# LMG1025_Flasher_Shield.net
KiCad netlist of a schematic drawn in EAGLE
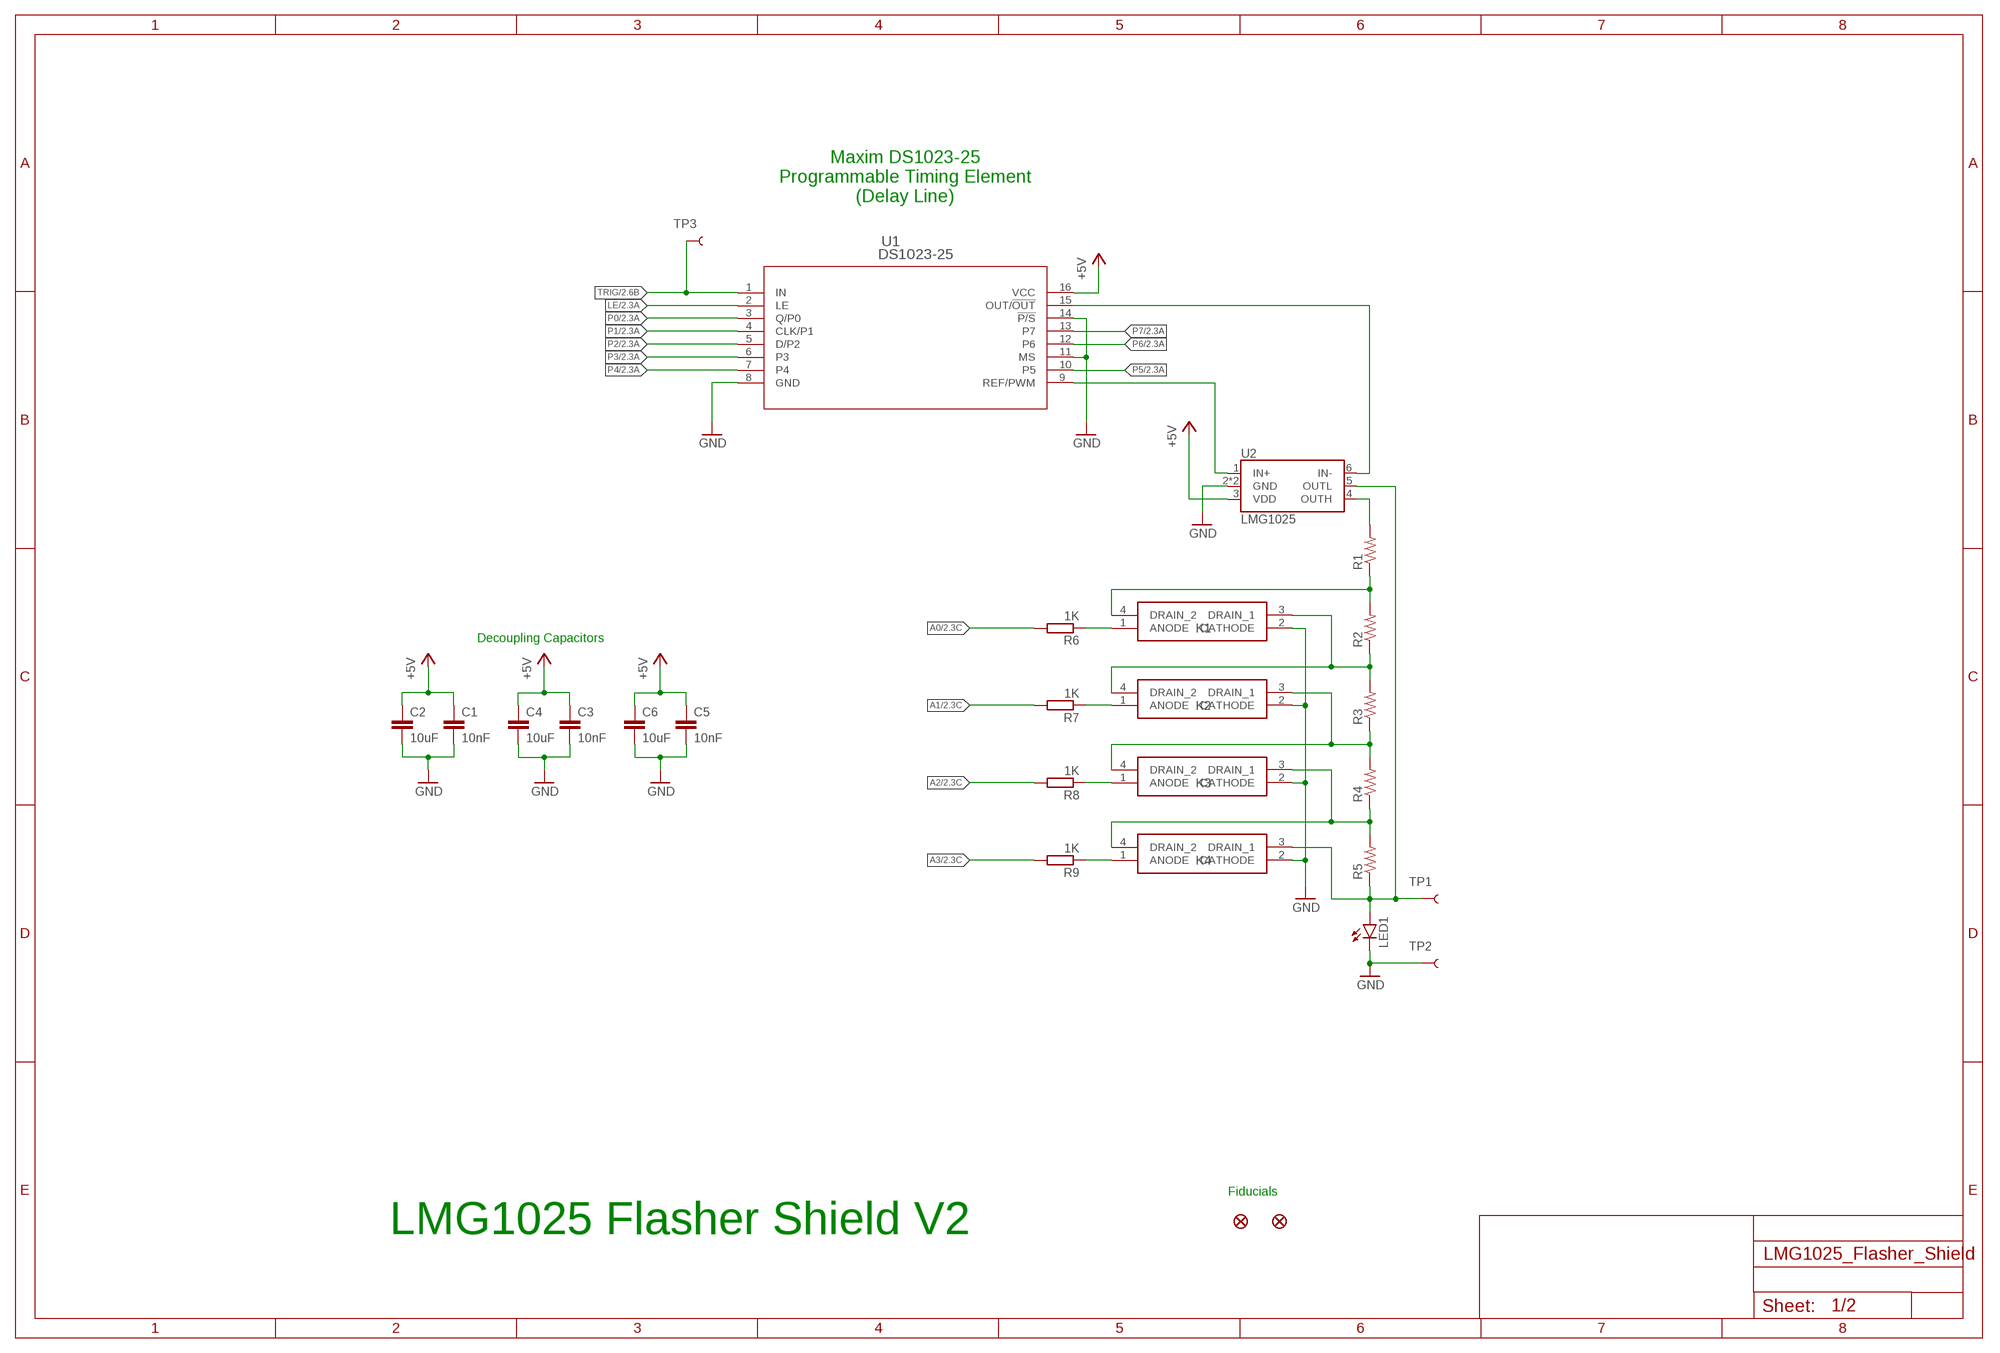
[diagram p0: schematic, sheet 1]
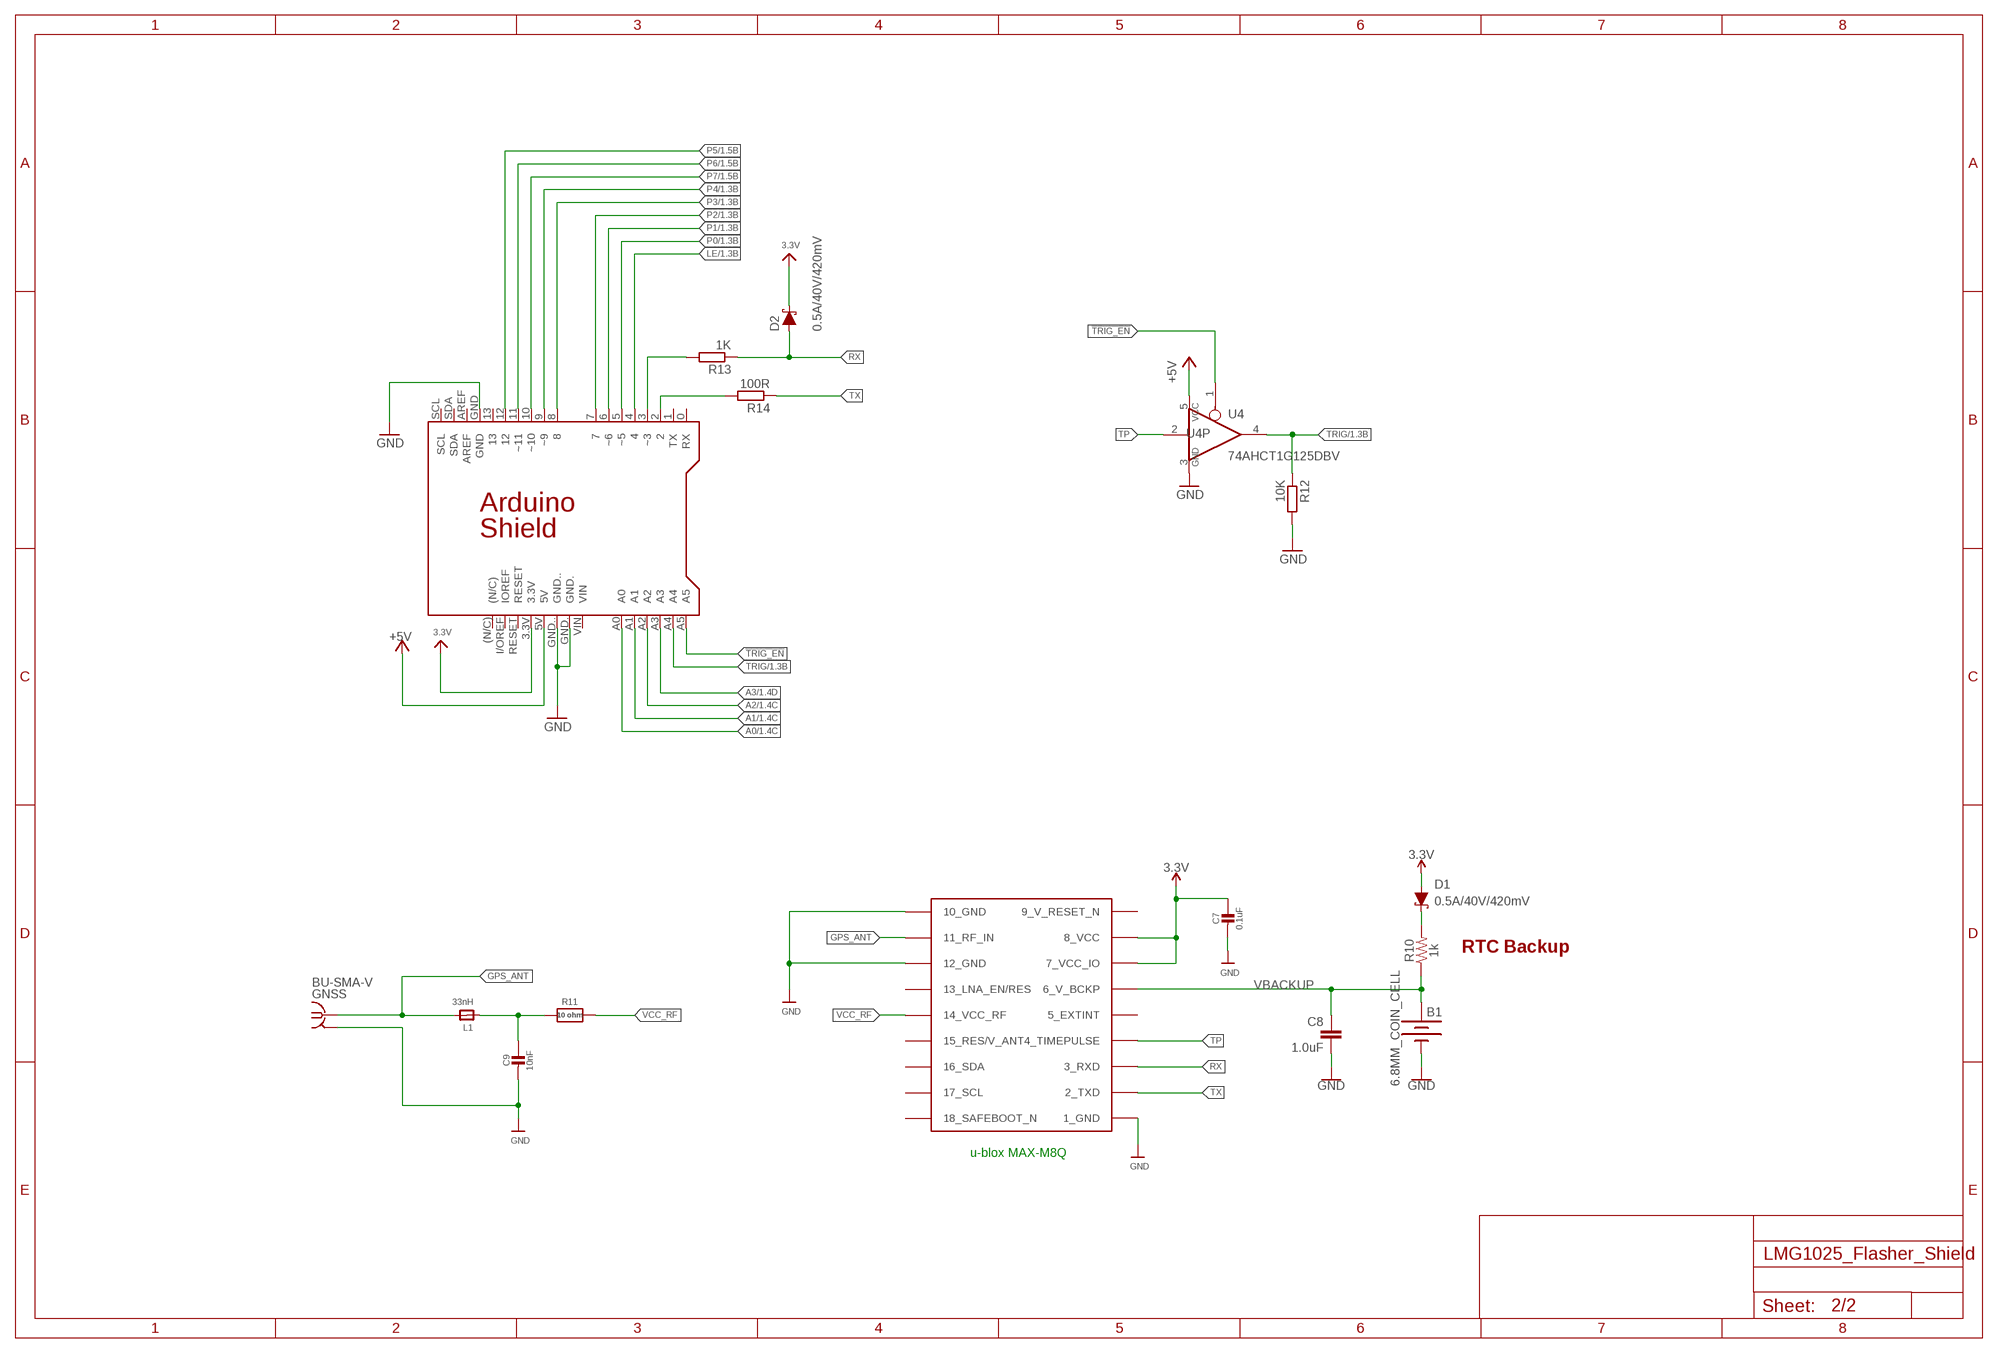
[diagram p1: schematic, sheet 2]

(export (version "E")
  (design (tool "Eeschema 10.0.6"))
  (components
    (comp (ref "B1")
      (value "6.8MM_COIN_CELL")
      (footprint "eagle-import:BATTCON-6.8MM")
      (libsource (lib "eagle-import") (part "BATTERY-6.8MM_SMD"))
    )
    (comp (ref "C7")
      (value "0.1uF")
      (footprint "eagle-import:0805-NO")
      (libsource (lib "eagle-import") (part "CAP_CERAMIC0805-NOOUTLINE"))
    )
    (comp (ref "C8")
      (value "1.0uF")
      (footprint "eagle-import:0603")
      (libsource (lib "eagle-import") (part "1.0UF-0603-16V-10%"))
    )
    (comp (ref "C9")
      (value "10nF")
      (footprint "eagle-import:0805-NO")
      (libsource (lib "eagle-import") (part "CAP_CERAMIC0805-NOOUTLINE"))
    )
    (comp (ref "D1")
      (value "0.5A/40V/420mV")
      (footprint "eagle-import:SOD-323")
      (libsource (lib "eagle-import") (part "DIODE-SCHOTTKY-PMEG4005EJ"))
    )
    (comp (ref "D2")
      (value "0.5A/40V/420mV")
      (footprint "eagle-import:SOD-323")
      (libsource (lib "eagle-import") (part "DIODE-SCHOTTKY-PMEG4005EJ"))
    )
    (comp (ref "GNSS")
      (value "BU-SMA-V")
      (footprint "eagle-import:BU-SMA-V")
      (libsource (lib "eagle-import") (part "BU-SMA-V"))
    )
    (comp (ref "L1")
      (value "33nH")
      (footprint "eagle-import:0805-NO")
      (libsource (lib "eagle-import") (part "FERRITE-0805NO"))
    )
    (comp (ref "PCB1")
      (value "CHEC_LED_DRIVER_SHIELD")
      (footprint "eagle-import:CHEC_LED_DRIVER_SHIELD")
      (libsource (lib "eagle-import") (part "CHEC_LED_DRIVER_SHIELD"))
    )
    (comp (ref "R10")
      (value "1k")
      (footprint "eagle-import:0603@1")
      (libsource (lib "eagle-import") (part "1KOHM-0603-1/10W-1%"))
    )
    (comp (ref "R11")
      (value "10 ohm")
      (footprint "eagle-import:0805-NO")
      (libsource (lib "eagle-import") (part "RESISTOR0805_NOOUTLINE"))
    )
    (comp (ref "R12")
      (value "10K")
      (footprint "eagle-import:R0603")
      (libsource (lib "eagle-import") (part "R-EU_R0603"))
    )
    (comp (ref "R13")
      (value "1K")
      (footprint "eagle-import:R0603")
      (libsource (lib "eagle-import") (part "R-EU_R0603"))
    )
    (comp (ref "R14")
      (value "100R")
      (footprint "eagle-import:R0603")
      (libsource (lib "eagle-import") (part "R-EU_R0603"))
    )
    (comp (ref "U3")
      (value "MAX-M8")
      (footprint "eagle-import:MAX-M8")
      (libsource (lib "eagle-import") (part "MAX-M8"))
    )
    (comp (ref "U4")
      (value "74AHCT1G125DBV")
      (footprint "eagle-import:SOT23-5")
      (libsource (lib "eagle-import") (part "741G125DBVAHCT"))
    )
    (comp (ref "C1")
      (value "10nF")
      (footprint "eagle-import:C0805")
      (libsource (lib "eagle-import") (part "C-EUC0805"))
    )
    (comp (ref "C2")
      (value "10uF")
      (footprint "eagle-import:C0805")
      (libsource (lib "eagle-import") (part "C-EUC0805"))
    )
    (comp (ref "C3")
      (value "10nF")
      (footprint "eagle-import:C0805")
      (libsource (lib "eagle-import") (part "C-EUC0805"))
    )
    (comp (ref "C4")
      (value "10uF")
      (footprint "eagle-import:C0805")
      (libsource (lib "eagle-import") (part "C-EUC0805"))
    )
    (comp (ref "C5")
      (value "10nF")
      (footprint "eagle-import:C0805")
      (libsource (lib "eagle-import") (part "C-EUC0805"))
    )
    (comp (ref "C6")
      (value "10uF")
      (footprint "eagle-import:C0805")
      (libsource (lib "eagle-import") (part "C-EUC0805"))
    )
    (comp (ref "FD1")
      (value "FIDUCIAL1X2")
      (footprint "eagle-import:FIDUCIAL-1X2")
      (libsource (lib "eagle-import") (part "FIDUCIAL1X2"))
    )
    (comp (ref "FD2")
      (value "FIDUCIAL1X2")
      (footprint "eagle-import:FIDUCIAL-1X2")
      (libsource (lib "eagle-import") (part "FIDUCIAL1X2"))
    )
    (comp (ref "K1")
      (value "TLP3475R(TP,F")
      (footprint "eagle-import:TLP3475RTPF")
      (fields (field (name "MOUSER_PART_NUMBER") "757-TLP3475RTPF"))
      (libsource (lib "eagle-import") (part "TLP3475R(TP,F"))
    )
    (comp (ref "K2")
      (value "TLP3475R(TP,F")
      (footprint "eagle-import:TLP3475RTPF")
      (fields (field (name "MOUSER_PART_NUMBER") "757-TLP3475RTPF"))
      (libsource (lib "eagle-import") (part "TLP3475R(TP,F"))
    )
    (comp (ref "K3")
      (value "TLP3475R(TP,F")
      (footprint "eagle-import:TLP3475RTPF")
      (fields (field (name "MOUSER_PART_NUMBER") "757-TLP3475RTPF"))
      (libsource (lib "eagle-import") (part "TLP3475R(TP,F"))
    )
    (comp (ref "K4")
      (value "TLP3475R(TP,F")
      (footprint "eagle-import:TLP3475RTPF")
      (fields (field (name "MOUSER_PART_NUMBER") "757-TLP3475RTPF"))
      (libsource (lib "eagle-import") (part "TLP3475R(TP,F"))
    )
    (comp (ref "LED1")
      (value "LED3MM")
      (footprint "eagle-import:LED3MM")
      (libsource (lib "eagle-import") (part "LED3MM"))
    )
    (comp (ref "R1")
      (value "RESISTOR0805-RES")
      (footprint "eagle-import:0805")
      (libsource (lib "eagle-import") (part "RESISTOR0805-RES"))
    )
    (comp (ref "R2")
      (value "RESISTOR0805-RES")
      (footprint "eagle-import:0805")
      (libsource (lib "eagle-import") (part "RESISTOR0805-RES"))
    )
    (comp (ref "R3")
      (value "RESISTOR0805-RES")
      (footprint "eagle-import:0805")
      (libsource (lib "eagle-import") (part "RESISTOR0805-RES"))
    )
    (comp (ref "R4")
      (value "RESISTOR0805-RES")
      (footprint "eagle-import:0805")
      (libsource (lib "eagle-import") (part "RESISTOR0805-RES"))
    )
    (comp (ref "R5")
      (value "RESISTOR0805-RES")
      (footprint "eagle-import:0805")
      (libsource (lib "eagle-import") (part "RESISTOR0805-RES"))
    )
    (comp (ref "R6")
      (value "1K")
      (footprint "eagle-import:R0603")
      (libsource (lib "eagle-import") (part "R-EU_R0603"))
    )
    (comp (ref "R7")
      (value "1K")
      (footprint "eagle-import:R0603")
      (libsource (lib "eagle-import") (part "R-EU_R0603"))
    )
    (comp (ref "R8")
      (value "1K")
      (footprint "eagle-import:R0603")
      (libsource (lib "eagle-import") (part "R-EU_R0603"))
    )
    (comp (ref "R9")
      (value "1K")
      (footprint "eagle-import:R0603")
      (libsource (lib "eagle-import") (part "R-EU_R0603"))
    )
    (comp (ref "TP1")
      (value "TEST-POINTPOGO_PTH")
      (footprint "eagle-import:1X01_NO_SILK")
      (libsource (lib "eagle-import") (part "TEST-POINTPOGO_PTH"))
    )
    (comp (ref "TP2")
      (value "TEST-POINTPOGO_PTH")
      (footprint "eagle-import:1X01_NO_SILK")
      (libsource (lib "eagle-import") (part "TEST-POINTPOGO_PTH"))
    )
    (comp (ref "TP3")
      (value "TEST-POINTPOGO_PTH")
      (footprint "eagle-import:1X01_NO_SILK")
      (libsource (lib "eagle-import") (part "TEST-POINTPOGO_PTH"))
    )
    (comp (ref "U1")
      (value "DS1023-25")
      (footprint "eagle-import:21-0042B_16")
      (fields (field (name "MANUFACTURER_PART_NUMBER") "DS102325"))
      (libsource (lib "eagle-import") (part "DS1023-25"))
    )
    (comp (ref "U2")
      (value "LMG1025")
      (footprint "eagle-import:LMG1025")
      (libsource (lib "eagle-import") (part "LMG1025"))
    )
  )
  (nets
    (net (code "1") (name "+5V") (class "Default")
      (node (ref "C1") (pin "1") (pinfunction "1_1") (pintype "passive"))
      (node (ref "C2") (pin "1") (pinfunction "1_1") (pintype "passive"))
      (node (ref "C3") (pin "1") (pinfunction "1_1") (pintype "passive"))
      (node (ref "C4") (pin "1") (pinfunction "1_1") (pintype "passive"))
      (node (ref "C5") (pin "1") (pinfunction "1_1") (pintype "passive"))
      (node (ref "C6") (pin "1") (pinfunction "1_1") (pintype "passive"))
      (node (ref "PCB1") (pin "5V") (pinfunction "5V_5V") (pintype "bidirectional"))
      (node (ref "U1") (pin "16") (pinfunction "VCC_16") (pintype "power_in"))
      (node (ref "U2") (pin "3") (pinfunction "VDD_3") (pintype "power_in"))
      (node (ref "U4") (pin "5") (pinfunction "VCC_5") (pintype "power_in"))
    )
    (net (code "2") (name "3.3V") (class "Default")
      (node (ref "C7") (pin "1") (pinfunction "1_1") (pintype "passive"))
      (node (ref "D1") (pin "A") (pinfunction "A_A") (pintype "passive"))
      (node (ref "D2") (pin "C") (pinfunction "C_C") (pintype "passive"))
      (node (ref "PCB1") (pin "3.3V") (pinfunction "3.3V_3.3V") (pintype "bidirectional"))
      (node (ref "U3") (pin "7_VCC_IO") (pinfunction "7_VCC_IO_7_VCC_IO") (pintype "power_in"))
      (node (ref "U3") (pin "8_VCC") (pinfunction "8_VCC_8_VCC") (pintype "power_in"))
    )
    (net (code "3") (name "9_V_RESET_N") (class "Default")
      (node (ref "U3") (pin "9_RESET_N") (pinfunction "9_V_RESET_N_9_RESET_N") (pintype "power_in"))
    )
    (net (code "4") (name "A0") (class "Default")
      (node (ref "PCB1") (pin "A0") (pinfunction "A0_A0") (pintype "bidirectional"))
      (node (ref "R6") (pin "2") (pinfunction "2_2") (pintype "passive"))
    )
    (net (code "5") (name "A1") (class "Default")
      (node (ref "PCB1") (pin "A1") (pinfunction "A1_A1") (pintype "bidirectional"))
      (node (ref "R7") (pin "2") (pinfunction "2_2") (pintype "passive"))
    )
    (net (code "6") (name "A2") (class "Default")
      (node (ref "PCB1") (pin "A2") (pinfunction "A2_A2") (pintype "bidirectional"))
      (node (ref "R8") (pin "2") (pinfunction "2_2") (pintype "passive"))
    )
    (net (code "7") (name "A3") (class "Default")
      (node (ref "PCB1") (pin "A3") (pinfunction "A3_A3") (pintype "bidirectional"))
      (node (ref "R9") (pin "2") (pinfunction "2_2") (pintype "passive"))
    )
    (net (code "8") (name "GND") (class "Default")
      (node (ref "B1") (pin "-") (pinfunction "-_-") (pintype "power_in"))
      (node (ref "C1") (pin "2") (pinfunction "2_2") (pintype "passive"))
      (node (ref "C2") (pin "2") (pinfunction "2_2") (pintype "passive"))
      (node (ref "C3") (pin "2") (pinfunction "2_2") (pintype "passive"))
      (node (ref "C4") (pin "2") (pinfunction "2_2") (pintype "passive"))
      (node (ref "C5") (pin "2") (pinfunction "2_2") (pintype "passive"))
      (node (ref "C6") (pin "2") (pinfunction "2_2") (pintype "passive"))
      (node (ref "C7") (pin "2") (pinfunction "2_2") (pintype "passive"))
      (node (ref "C8") (pin "2") (pinfunction "2_2") (pintype "passive"))
      (node (ref "C9") (pin "2") (pinfunction "2_2") (pintype "passive"))
      (node (ref "GNSS") (pin "2") (pinfunction "2_2") (pintype "passive"))
      (node (ref "GNSS") (pin "3") (pinfunction "2_3") (pintype "passive"))
      (node (ref "GNSS") (pin "4") (pinfunction "2_4") (pintype "passive"))
      (node (ref "GNSS") (pin "5") (pinfunction "2_5") (pintype "passive"))
      (node (ref "K1") (pin "2") (pinfunction "CATHODE_2") (pintype "bidirectional"))
      (node (ref "K2") (pin "2") (pinfunction "CATHODE_2") (pintype "bidirectional"))
      (node (ref "K3") (pin "2") (pinfunction "CATHODE_2") (pintype "bidirectional"))
      (node (ref "K4") (pin "2") (pinfunction "CATHODE_2") (pintype "bidirectional"))
      (node (ref "LED1") (pin "K") (pinfunction "C_K") (pintype "passive"))
      (node (ref "PCB1") (pin "GND") (pinfunction "GND_GND") (pintype "bidirectional"))
      (node (ref "PCB1") (pin "GND.") (pinfunction "GND._GND.") (pintype "bidirectional"))
      (node (ref "PCB1") (pin "GND..") (pinfunction "GND.._GND..") (pintype "bidirectional"))
      (node (ref "R12") (pin "2") (pinfunction "2_2") (pintype "passive"))
      (node (ref "TP2") (pin "1") (pinfunction "1_1") (pintype "bidirectional"))
      (node (ref "U1") (pin "11") (pinfunction "MS_11") (pintype "passive"))
      (node (ref "U1") (pin "14") (pinfunction "~{P/S}_14") (pintype "passive"))
      (node (ref "U1") (pin "8") (pinfunction "GND_8") (pintype "power_in"))
      (node (ref "U2") (pin "2") (pinfunction "GND_2") (pintype "power_in"))
      (node (ref "U2") (pin "PAD") (pinfunction "GND_PAD") (pintype "power_in"))
      (node (ref "U3") (pin "10_GND") (pinfunction "10_GND_10_GND") (pintype "power_in"))
      (node (ref "U3") (pin "12_GND") (pinfunction "12_GND_12_GND") (pintype "power_in"))
      (node (ref "U3") (pin "1_GND") (pinfunction "1_GND_1_GND") (pintype "power_in"))
      (node (ref "U4") (pin "3") (pinfunction "GND_3") (pintype "power_in"))
    )
    (net (code "9") (name "GPS_ANT") (class "Default")
      (node (ref "GNSS") (pin "1") (pinfunction "1_1") (pintype "passive"))
      (node (ref "L1") (pin "2") (pinfunction "P$2_2") (pintype "passive"))
      (node (ref "U3") (pin "11_RF_IN") (pinfunction "11_RF_IN_11_RF_IN") (pintype "bidirectional"))
    )
    (net (code "10") (name "LE") (class "Default")
      (node (ref "PCB1") (pin "4") (pinfunction "4_4") (pintype "bidirectional"))
      (node (ref "U1") (pin "2") (pinfunction "LE_2") (pintype "passive"))
    )
    (net (code "11") (name "Net-(D1-PadC)") (class "Default")
      (node (ref "D1") (pin "C") (pinfunction "C_C") (pintype "passive"))
      (node (ref "R10") (pin "2") (pinfunction "2_2") (pintype "passive"))
    )
    (net (code "12") (name "Net-(K1-ANODE)") (class "Default")
      (node (ref "K1") (pin "1") (pinfunction "ANODE_1") (pintype "bidirectional"))
      (node (ref "R6") (pin "1") (pinfunction "1_1") (pintype "passive"))
    )
    (net (code "13") (name "Net-(K1-DRAIN_1)") (class "Default")
      (node (ref "K1") (pin "3") (pinfunction "DRAIN_1_3") (pintype "bidirectional"))
      (node (ref "K2") (pin "4") (pinfunction "DRAIN_2_4") (pintype "bidirectional"))
      (node (ref "R2") (pin "1") (pinfunction "1_1") (pintype "passive"))
      (node (ref "R3") (pin "2") (pinfunction "2_2") (pintype "passive"))
    )
    (net (code "14") (name "Net-(K1-DRAIN_2)") (class "Default")
      (node (ref "K1") (pin "4") (pinfunction "DRAIN_2_4") (pintype "bidirectional"))
      (node (ref "R1") (pin "1") (pinfunction "1_1") (pintype "passive"))
      (node (ref "R2") (pin "2") (pinfunction "2_2") (pintype "passive"))
    )
    (net (code "15") (name "Net-(K2-ANODE)") (class "Default")
      (node (ref "K2") (pin "1") (pinfunction "ANODE_1") (pintype "bidirectional"))
      (node (ref "R7") (pin "1") (pinfunction "1_1") (pintype "passive"))
    )
    (net (code "16") (name "Net-(K2-DRAIN_1)") (class "Default")
      (node (ref "K2") (pin "3") (pinfunction "DRAIN_1_3") (pintype "bidirectional"))
      (node (ref "K3") (pin "4") (pinfunction "DRAIN_2_4") (pintype "bidirectional"))
      (node (ref "R3") (pin "1") (pinfunction "1_1") (pintype "passive"))
      (node (ref "R4") (pin "2") (pinfunction "2_2") (pintype "passive"))
    )
    (net (code "17") (name "Net-(K3-ANODE)") (class "Default")
      (node (ref "K3") (pin "1") (pinfunction "ANODE_1") (pintype "bidirectional"))
      (node (ref "R8") (pin "1") (pinfunction "1_1") (pintype "passive"))
    )
    (net (code "18") (name "Net-(K3-DRAIN_1)") (class "Default")
      (node (ref "K3") (pin "3") (pinfunction "DRAIN_1_3") (pintype "bidirectional"))
      (node (ref "K4") (pin "4") (pinfunction "DRAIN_2_4") (pintype "bidirectional"))
      (node (ref "R4") (pin "1") (pinfunction "1_1") (pintype "passive"))
      (node (ref "R5") (pin "2") (pinfunction "2_2") (pintype "passive"))
    )
    (net (code "19") (name "Net-(K4-ANODE)") (class "Default")
      (node (ref "K4") (pin "1") (pinfunction "ANODE_1") (pintype "bidirectional"))
      (node (ref "R9") (pin "1") (pinfunction "1_1") (pintype "passive"))
    )
    (net (code "20") (name "Net-(K4-DRAIN_1)") (class "Default")
      (node (ref "K4") (pin "3") (pinfunction "DRAIN_1_3") (pintype "bidirectional"))
      (node (ref "LED1") (pin "A") (pinfunction "A_A") (pintype "passive"))
      (node (ref "R5") (pin "1") (pinfunction "1_1") (pintype "passive"))
      (node (ref "TP1") (pin "1") (pinfunction "1_1") (pintype "bidirectional"))
      (node (ref "U2") (pin "5") (pinfunction "OUTL_5") (pintype "output"))
    )
    (net (code "21") (name "Net-(L1-P$1)") (class "Default")
      (node (ref "C9") (pin "1") (pinfunction "1_1") (pintype "passive"))
      (node (ref "L1") (pin "1") (pinfunction "P$1_1") (pintype "passive"))
      (node (ref "R11") (pin "1") (pinfunction "1_1") (pintype "passive"))
    )
    (net (code "22") (name "Net-(PCB1-Pad2)") (class "Default")
      (node (ref "PCB1") (pin "2") (pinfunction "2_2") (pintype "bidirectional"))
      (node (ref "R14") (pin "2") (pinfunction "2_2") (pintype "passive"))
    )
    (net (code "23") (name "Net-(PCB1-~{3})") (class "Default")
      (node (ref "PCB1") (pin "3") (pinfunction "~{3}_3") (pintype "bidirectional"))
      (node (ref "R13") (pin "2") (pinfunction "2_2") (pintype "passive"))
    )
    (net (code "24") (name "Net-(U1-OUT{slash}~{OUT})") (class "Default")
      (node (ref "U1") (pin "15") (pinfunction "OUT/~{OUT}_15") (pintype "passive"))
      (node (ref "U2") (pin "6") (pinfunction "IN-_6") (pintype "input"))
    )
    (net (code "25") (name "Net-(U1-REF{slash}PWM)") (class "Default")
      (node (ref "U1") (pin "9") (pinfunction "REF/PWM_9") (pintype "passive"))
      (node (ref "U2") (pin "1") (pinfunction "IN+_1") (pintype "input"))
    )
    (net (code "26") (name "Net-(U2-OUTH)") (class "Default")
      (node (ref "R1") (pin "2") (pinfunction "2_2") (pintype "passive"))
      (node (ref "U2") (pin "4") (pinfunction "OUTH_4") (pintype "output"))
    )
    (net (code "27") (name "P0") (class "Default")
      (node (ref "PCB1") (pin "5") (pinfunction "~{5}_5") (pintype "bidirectional"))
      (node (ref "U1") (pin "3") (pinfunction "Q/P0_3") (pintype "passive"))
    )
    (net (code "28") (name "P1") (class "Default")
      (node (ref "PCB1") (pin "6") (pinfunction "~{6}_6") (pintype "bidirectional"))
      (node (ref "U1") (pin "4") (pinfunction "CLK/P1_4") (pintype "passive"))
    )
    (net (code "29") (name "P2") (class "Default")
      (node (ref "PCB1") (pin "7") (pinfunction "7_7") (pintype "bidirectional"))
      (node (ref "U1") (pin "5") (pinfunction "D/P2_5") (pintype "passive"))
    )
    (net (code "30") (name "P3") (class "Default")
      (node (ref "PCB1") (pin "8") (pinfunction "8_8") (pintype "bidirectional"))
      (node (ref "U1") (pin "6") (pinfunction "P3_6") (pintype "passive"))
    )
    (net (code "31") (name "P4") (class "Default")
      (node (ref "PCB1") (pin "9") (pinfunction "~{9}_9") (pintype "bidirectional"))
      (node (ref "U1") (pin "7") (pinfunction "P4_7") (pintype "passive"))
    )
    (net (code "32") (name "P5") (class "Default")
      (node (ref "PCB1") (pin "12") (pinfunction "12_12") (pintype "bidirectional"))
      (node (ref "U1") (pin "10") (pinfunction "P5_10") (pintype "passive"))
    )
    (net (code "33") (name "P6") (class "Default")
      (node (ref "PCB1") (pin "11") (pinfunction "~{11}_11") (pintype "bidirectional"))
      (node (ref "U1") (pin "12") (pinfunction "P6_12") (pintype "passive"))
    )
    (net (code "34") (name "P7") (class "Default")
      (node (ref "PCB1") (pin "10") (pinfunction "~{10}_10") (pintype "bidirectional"))
      (node (ref "U1") (pin "13") (pinfunction "P7_13") (pintype "passive"))
    )
    (net (code "35") (name "RX") (class "Default")
      (node (ref "D2") (pin "A") (pinfunction "A_A") (pintype "passive"))
      (node (ref "R13") (pin "1") (pinfunction "1_1") (pintype "passive"))
      (node (ref "U3") (pin "3_RXD") (pinfunction "3_RXD_3_RXD") (pintype "bidirectional"))
    )
    (net (code "36") (name "TP") (class "Default")
      (node (ref "U3") (pin "4_TIMEPULSE") (pinfunction "4_TIMEPULSE_4_TIMEPULSE") (pintype "bidirectional"))
      (node (ref "U4") (pin "2") (pinfunction "I_2") (pintype "input"))
    )
    (net (code "37") (name "TRIG") (class "Default")
      (node (ref "PCB1") (pin "A4") (pinfunction "A4_A4") (pintype "bidirectional"))
      (node (ref "R12") (pin "1") (pinfunction "1_1") (pintype "passive"))
      (node (ref "TP3") (pin "1") (pinfunction "1_1") (pintype "bidirectional"))
      (node (ref "U1") (pin "1") (pinfunction "IN_1") (pintype "input"))
      (node (ref "U4") (pin "4") (pinfunction "O_4") (pintype "tri_state"))
    )
    (net (code "38") (name "TX") (class "Default")
      (node (ref "R14") (pin "1") (pinfunction "1_1") (pintype "passive"))
      (node (ref "U3") (pin "2_TXD") (pinfunction "2_TXD_2_TXD") (pintype "bidirectional"))
    )
    (net (code "39") (name "VBACKUP") (class "Default")
      (node (ref "B1") (pin "+") (pinfunction "+_+") (pintype "power_in"))
      (node (ref "C8") (pin "1") (pinfunction "1_1") (pintype "passive"))
      (node (ref "R10") (pin "1") (pinfunction "1_1") (pintype "passive"))
      (node (ref "U3") (pin "6_V_BCKP") (pinfunction "6_V_BCKP_6_V_BCKP") (pintype "bidirectional"))
    )
    (net (code "40") (name "VCC_RF") (class "Default")
      (node (ref "R11") (pin "2") (pinfunction "2_2") (pintype "passive"))
      (node (ref "U3") (pin "14_VCC_RF") (pinfunction "14_VCC_RF_14_VCC_RF") (pintype "bidirectional"))
    )
    (net (code "41") (name "unconnected-(PCB1-IOREF-PadI{slash}OREF)") (class "Default")
      (node (ref "PCB1") (pin "I/OREF") (pinfunction "IOREF_I/OREF") (pintype "bidirectional"))
    )
    (net (code "42") (name "unconnected-(PCB1-Pad(N{slash}C))") (class "Default")
      (node (ref "PCB1") (pin "(N/C)") (pinfunction "(N/C)_(N/C)") (pintype "bidirectional"))
    )
    (net (code "43") (name "unconnected-(PCB1-Pad13)") (class "Default")
      (node (ref "PCB1") (pin "13") (pinfunction "13_13") (pintype "bidirectional"))
    )
    (net (code "44") (name "unconnected-(PCB1-PadAREF)") (class "Default")
      (node (ref "PCB1") (pin "AREF") (pinfunction "AREF_AREF") (pintype "bidirectional"))
    )
    (net (code "45") (name "unconnected-(PCB1-PadRESET)") (class "Default")
      (node (ref "PCB1") (pin "RESET") (pinfunction "RESET_RESET") (pintype "bidirectional"))
    )
    (net (code "46") (name "unconnected-(PCB1-PadSCL)") (class "Default")
      (node (ref "PCB1") (pin "SCL") (pinfunction "SCL_SCL") (pintype "bidirectional"))
    )
    (net (code "47") (name "unconnected-(PCB1-PadSDA)") (class "Default")
      (node (ref "PCB1") (pin "SDA") (pinfunction "SDA_SDA") (pintype "bidirectional"))
    )
    (net (code "48") (name "unconnected-(PCB1-PadVIN)") (class "Default")
      (node (ref "PCB1") (pin "VIN") (pinfunction "VIN_VIN") (pintype "bidirectional"))
    )
    (net (code "49") (name "unconnected-(PCB1-RX-Pad0)") (class "Default")
      (node (ref "PCB1") (pin "0") (pinfunction "RX_0") (pintype "bidirectional"))
    )
    (net (code "50") (name "unconnected-(PCB1-TX-Pad1)") (class "Default")
      (node (ref "PCB1") (pin "1") (pinfunction "TX_1") (pintype "bidirectional"))
    )
    (net (code "51") (name "unconnected-(U3-13_LNA_EN{slash}RES-Pad13_LNA_EN)") (class "Default")
      (node (ref "U3") (pin "13_LNA_EN") (pinfunction "13_LNA_EN/RES_13_LNA_EN") (pintype "bidirectional"))
    )
    (net (code "52") (name "unconnected-(U3-15_RES{slash}V_ANT-Pad15_V_ANT{slash}RESERVED)") (class "Default")
      (node (ref "U3") (pin "15_V_ANT/RESERVED") (pinfunction "15_RES/V_ANT_15_V_ANT/RESERVED") (pintype "bidirectional"))
    )
    (net (code "53") (name "unconnected-(U3-Pad5_EXTINT)") (class "Default")
      (node (ref "U3") (pin "5_EXTINT") (pinfunction "5_EXTINT_5_EXTINT") (pintype "bidirectional"))
    )
    (net (code "54") (name "unconnected-(U3-Pad16_SDA)") (class "Default")
      (node (ref "U3") (pin "16_SDA") (pinfunction "16_SDA_16_SDA") (pintype "bidirectional"))
    )
    (net (code "55") (name "unconnected-(U3-Pad17_SCL)") (class "Default")
      (node (ref "U3") (pin "17_SCL") (pinfunction "17_SCL_17_SCL") (pintype "bidirectional"))
    )
    (net (code "56") (name "unconnected-(U3-Pad18_SAFEBOOT_N)") (class "Default")
      (node (ref "U3") (pin "18_SAFEBOOT_N") (pinfunction "18_SAFEBOOT_N_18_SAFEBOOT_N") (pintype "bidirectional"))
    )
    (net (code "57") (name "~{TRIG_EN}") (class "Default")
      (node (ref "PCB1") (pin "A5") (pinfunction "A5_A5") (pintype "bidirectional"))
      (node (ref "U4") (pin "1") (pinfunction "OE_1") (pintype "input"))
    )
  )
)
